# wirelessSensor_0_1.net
KiCad netlist of a schematic drawn in EAGLE
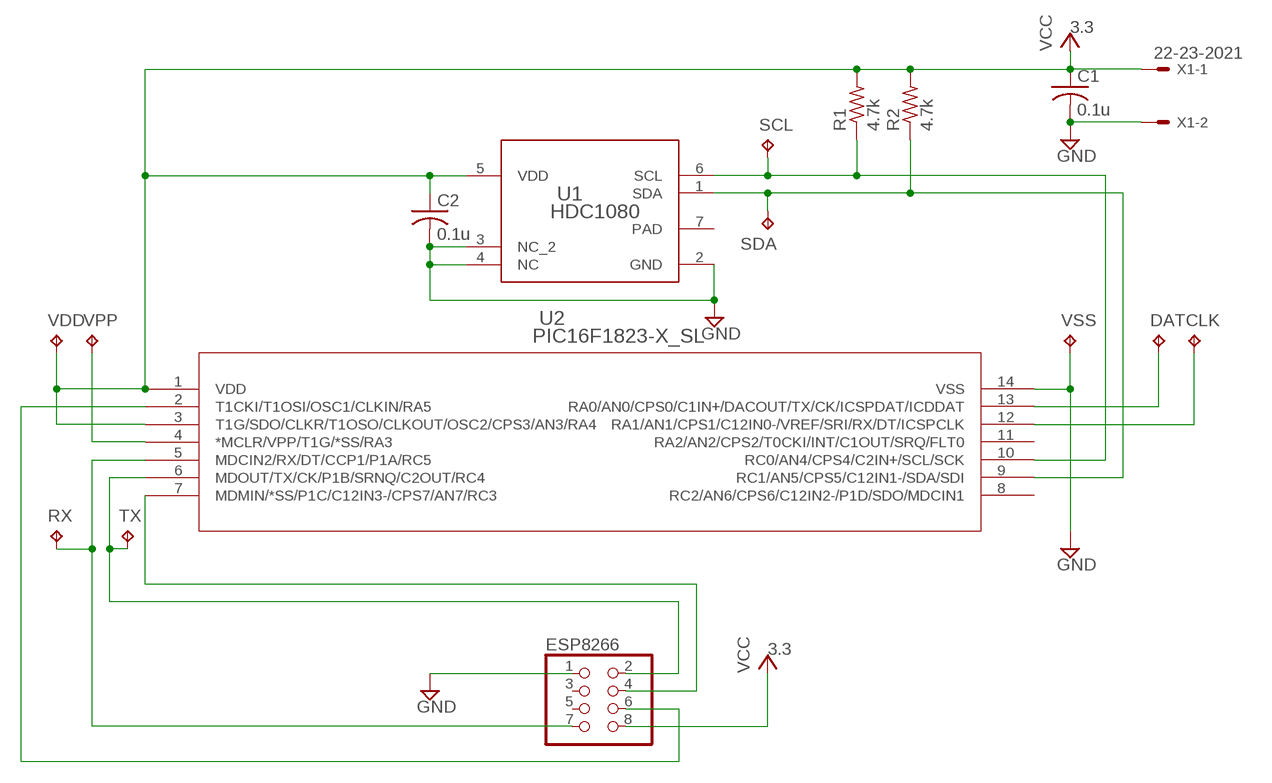
[diagram p0: schematic, sheet 1]

(export (version "E")
  (design (tool "Eeschema 10.0.6"))
  (components
    (comp (ref "C1")
      (value "0.1u")
      (footprint "eagle-import:C0603")
      (libsource (lib "eagle-import") (part "C-USC0603"))
    )
    (comp (ref "C2")
      (value "0.1u")
      (footprint "eagle-import:C0603")
      (libsource (lib "eagle-import") (part "C-USC0603"))
    )
    (comp (ref "CLK")
      (value "TPB1,27")
      (footprint "eagle-import:B1,27")
      (libsource (lib "eagle-import") (part "TPB1,27"))
    )
    (comp (ref "DAT")
      (value "TPB1,27")
      (footprint "eagle-import:B1,27")
      (libsource (lib "eagle-import") (part "TPB1,27"))
    )
    (comp (ref "ESP8266")
      (value "PINHD-2X4")
      (footprint "eagle-import:2X04")
      (libsource (lib "eagle-import") (part "PINHD-2X4"))
    )
    (comp (ref "R1")
      (value "4.7k")
      (footprint "eagle-import:R0603")
      (libsource (lib "eagle-import") (part "R-US_R0603"))
    )
    (comp (ref "R2")
      (value "4.7k")
      (footprint "eagle-import:R0603")
      (libsource (lib "eagle-import") (part "R-US_R0603"))
    )
    (comp (ref "RX")
      (value "TPB1,27")
      (footprint "eagle-import:B1,27")
      (libsource (lib "eagle-import") (part "TPB1,27"))
    )
    (comp (ref "SCL")
      (value "TPB1,27")
      (footprint "eagle-import:B1,27")
      (libsource (lib "eagle-import") (part "TPB1,27"))
    )
    (comp (ref "SDA")
      (value "TPB1,27")
      (footprint "eagle-import:B1,27")
      (libsource (lib "eagle-import") (part "TPB1,27"))
    )
    (comp (ref "TX")
      (value "TPB1,27")
      (footprint "eagle-import:B1,27")
      (libsource (lib "eagle-import") (part "TPB1,27"))
    )
    (comp (ref "U1")
      (value "HDC1080")
      (footprint "eagle-import:DMB0006A")
      (fields
        (field (name "ALTERNATEPARTNUMBER") "HDC1080DMBT")
        (field (name "MANUFACTURER") "Texas Instruments")
        (field (name "PARTNUMBER") "HDC1080DMBR")
      )
      (libsource (lib "eagle-import") (part "HDC1080DMBR"))
    )
    (comp (ref "U2")
      (value "PIC16F1823-X_SL")
      (footprint "eagle-import:SOIC14-N_MC")
      (libsource (lib "eagle-import") (part "PIC16F1823-X_SL"))
    )
    (comp (ref "VDD")
      (value "TPB1,27")
      (footprint "eagle-import:B1,27")
      (libsource (lib "eagle-import") (part "TPB1,27"))
    )
    (comp (ref "VPP")
      (value "TPB1,27")
      (footprint "eagle-import:B1,27")
      (libsource (lib "eagle-import") (part "TPB1,27"))
    )
    (comp (ref "VSS")
      (value "TPB1,27")
      (footprint "eagle-import:B1,27")
      (libsource (lib "eagle-import") (part "TPB1,27"))
    )
    (comp (ref "X1")
      (value "22-23-2021")
      (footprint "eagle-import:22-23-2021")
      (fields (field (name "MF") "MOLEX"))
      (libsource (lib "eagle-import") (part "22-23-2021"))
    )
  )
  (nets
    (net (code "1") (name "/PAD") (class "Default")
      (node (ref "U1") (pin "7") (pinfunction "PAD_7") (pintype "power_in"))
    )
    (net (code "2") (name "GND") (class "Default")
      (node (ref "C1") (pin "2") (pinfunction "2_2") (pintype "passive"))
      (node (ref "C2") (pin "2") (pinfunction "2_2") (pintype "passive"))
      (node (ref "ESP8266") (pin "1") (pinfunction "1_1") (pintype "passive"))
      (node (ref "U1") (pin "2") (pinfunction "GND_2") (pintype "power_in"))
      (node (ref "U1") (pin "3") (pinfunction "NC_2_3") (pintype "passive"))
      (node (ref "U1") (pin "4") (pinfunction "NC_4") (pintype "passive"))
      (node (ref "U2") (pin "14") (pinfunction "VSS_14") (pintype "power_in"))
      (node (ref "VSS") (pin "TP") (pinfunction "TP_TP") (pintype "input"))
      (node (ref "X1") (pin "2") (pinfunction "S_2") (pintype "passive"))
    )
    (net (code "3") (name "Net-(U1-SCL)") (class "Default")
      (node (ref "R1") (pin "1") (pinfunction "1_1") (pintype "passive"))
      (node (ref "SCL") (pin "TP") (pinfunction "TP_TP") (pintype "input"))
      (node (ref "U1") (pin "6") (pinfunction "SCL_6") (pintype "open_collector"))
      (node (ref "U2") (pin "10") (pinfunction "RC0/AN4/CPS4/C2IN+/SCL/SCK_10") (pintype "bidirectional"))
    )
    (net (code "4") (name "Net-(U1-SDA)") (class "Default")
      (node (ref "R2") (pin "1") (pinfunction "1_1") (pintype "passive"))
      (node (ref "SDA") (pin "TP") (pinfunction "TP_TP") (pintype "input"))
      (node (ref "U1") (pin "1") (pinfunction "SDA_1") (pintype "bidirectional"))
      (node (ref "U2") (pin "9") (pinfunction "RC1/AN5/CPS5/C12IN1-/SDA/SDI_9") (pintype "bidirectional"))
    )
    (net (code "5") (name "Net-(U2-*MCLR{slash}VPP{slash}T1G{slash}*SS{slash}RA3)") (class "Default")
      (node (ref "U2") (pin "4") (pinfunction "*MCLR/VPP/T1G/*SS/RA3_4") (pintype "bidirectional"))
      (node (ref "VPP") (pin "TP") (pinfunction "TP_TP") (pintype "input"))
    )
    (net (code "6") (name "Net-(U2-MDCIN2{slash}RX{slash}DT{slash}CCP1{slash}P1A{slash}RC5)") (class "Default")
      (node (ref "ESP8266") (pin "7") (pinfunction "7_7") (pintype "passive"))
      (node (ref "RX") (pin "TP") (pinfunction "TP_TP") (pintype "input"))
      (node (ref "U2") (pin "5") (pinfunction "MDCIN2/RX/DT/CCP1/P1A/RC5_5") (pintype "bidirectional"))
    )
    (net (code "7") (name "Net-(U2-MDMIN{slash}*SS{slash}P1C{slash}C12IN3-{slash}CPS7{slash}AN7{slash}RC3)") (class "Default")
      (node (ref "ESP8266") (pin "4") (pinfunction "4_4") (pintype "passive"))
      (node (ref "U2") (pin "7") (pinfunction "MDMIN/*SS/P1C/C12IN3-/CPS7/AN7/RC3_7") (pintype "bidirectional"))
    )
    (net (code "8") (name "Net-(U2-MDOUT{slash}TX{slash}CK{slash}P1B{slash}SRNQ{slash}C2OUT{slash}RC4)") (class "Default")
      (node (ref "ESP8266") (pin "2") (pinfunction "2_2") (pintype "passive"))
      (node (ref "TX") (pin "TP") (pinfunction "TP_TP") (pintype "input"))
      (node (ref "U2") (pin "6") (pinfunction "MDOUT/TX/CK/P1B/SRNQ/C2OUT/RC4_6") (pintype "bidirectional"))
    )
    (net (code "9") (name "Net-(U2-RA0{slash}AN0{slash}CPS0{slash}C1IN+{slash}DACOUT{slash}TX{slash}CK{slash}ICSPDAT{slash}ICDDAT)") (class "Default")
      (node (ref "DAT") (pin "TP") (pinfunction "TP_TP") (pintype "input"))
      (node (ref "U2") (pin "13") (pinfunction "RA0/AN0/CPS0/C1IN+/DACOUT/TX/CK/ICSPDAT/ICDDAT_13") (pintype "bidirectional"))
    )
    (net (code "10") (name "Net-(U2-RA1{slash}AN1{slash}CPS1{slash}C12IN0-{slash}VREF{slash}SRI{slash}RX{slash}DT{slash}ICSPCLK)") (class "Default")
      (node (ref "CLK") (pin "TP") (pinfunction "TP_TP") (pintype "input"))
      (node (ref "U2") (pin "12") (pinfunction "RA1/AN1/CPS1/C12IN0-/VREF/SRI/RX/DT/ICSPCLK_12") (pintype "bidirectional"))
    )
    (net (code "11") (name "Net-(U2-T1CKI{slash}T1OSI{slash}OSC1{slash}CLKIN{slash}RA5)") (class "Default")
      (node (ref "ESP8266") (pin "6") (pinfunction "6_6") (pintype "passive"))
      (node (ref "U2") (pin "2") (pinfunction "T1CKI/T1OSI/OSC1/CLKIN/RA5_2") (pintype "bidirectional"))
    )
    (net (code "12") (name "VCC") (class "Default")
      (node (ref "C1") (pin "1") (pinfunction "1_1") (pintype "passive"))
      (node (ref "C2") (pin "1") (pinfunction "1_1") (pintype "passive"))
      (node (ref "ESP8266") (pin "8") (pinfunction "8_8") (pintype "passive"))
      (node (ref "R1") (pin "2") (pinfunction "2_2") (pintype "passive"))
      (node (ref "R2") (pin "2") (pinfunction "2_2") (pintype "passive"))
      (node (ref "U1") (pin "5") (pinfunction "VDD_5") (pintype "power_in"))
      (node (ref "U2") (pin "1") (pinfunction "VDD_1") (pintype "power_in"))
      (node (ref "U2") (pin "3") (pinfunction "T1G/SDO/CLKR/T1OSO/CLKOUT/OSC2/CPS3/AN3/RA4_3") (pintype "bidirectional"))
      (node (ref "VDD") (pin "TP") (pinfunction "TP_TP") (pintype "input"))
      (node (ref "X1") (pin "1") (pinfunction "S_1") (pintype "passive"))
    )
    (net (code "13") (name "unconnected-(ESP8266-Pad3)") (class "Default")
      (node (ref "ESP8266") (pin "3") (pinfunction "3_3") (pintype "passive"))
    )
    (net (code "14") (name "unconnected-(ESP8266-Pad5)") (class "Default")
      (node (ref "ESP8266") (pin "5") (pinfunction "5_5") (pintype "passive"))
    )
    (net (code "15") (name "unconnected-(U2-RA2{slash}AN2{slash}CPS2{slash}T0CKI{slash}INT{slash}C1OUT{slash}SRQ{slash}FLT0-Pad11)") (class "Default")
      (node (ref "U2") (pin "11") (pinfunction "RA2/AN2/CPS2/T0CKI/INT/C1OUT/SRQ/FLT0_11") (pintype "bidirectional"))
    )
    (net (code "16") (name "unconnected-(U2-RC2{slash}AN6{slash}CPS6{slash}C12IN2-{slash}P1D{slash}SDO{slash}MDCIN1-Pad8)") (class "Default")
      (node (ref "U2") (pin "8") (pinfunction "RC2/AN6/CPS6/C12IN2-/P1D/SDO/MDCIN1_8") (pintype "bidirectional"))
    )
  )
)
